# Edison_Mezzanine_ArduinoPro.net
KiCad netlist of a schematic drawn in EAGLE
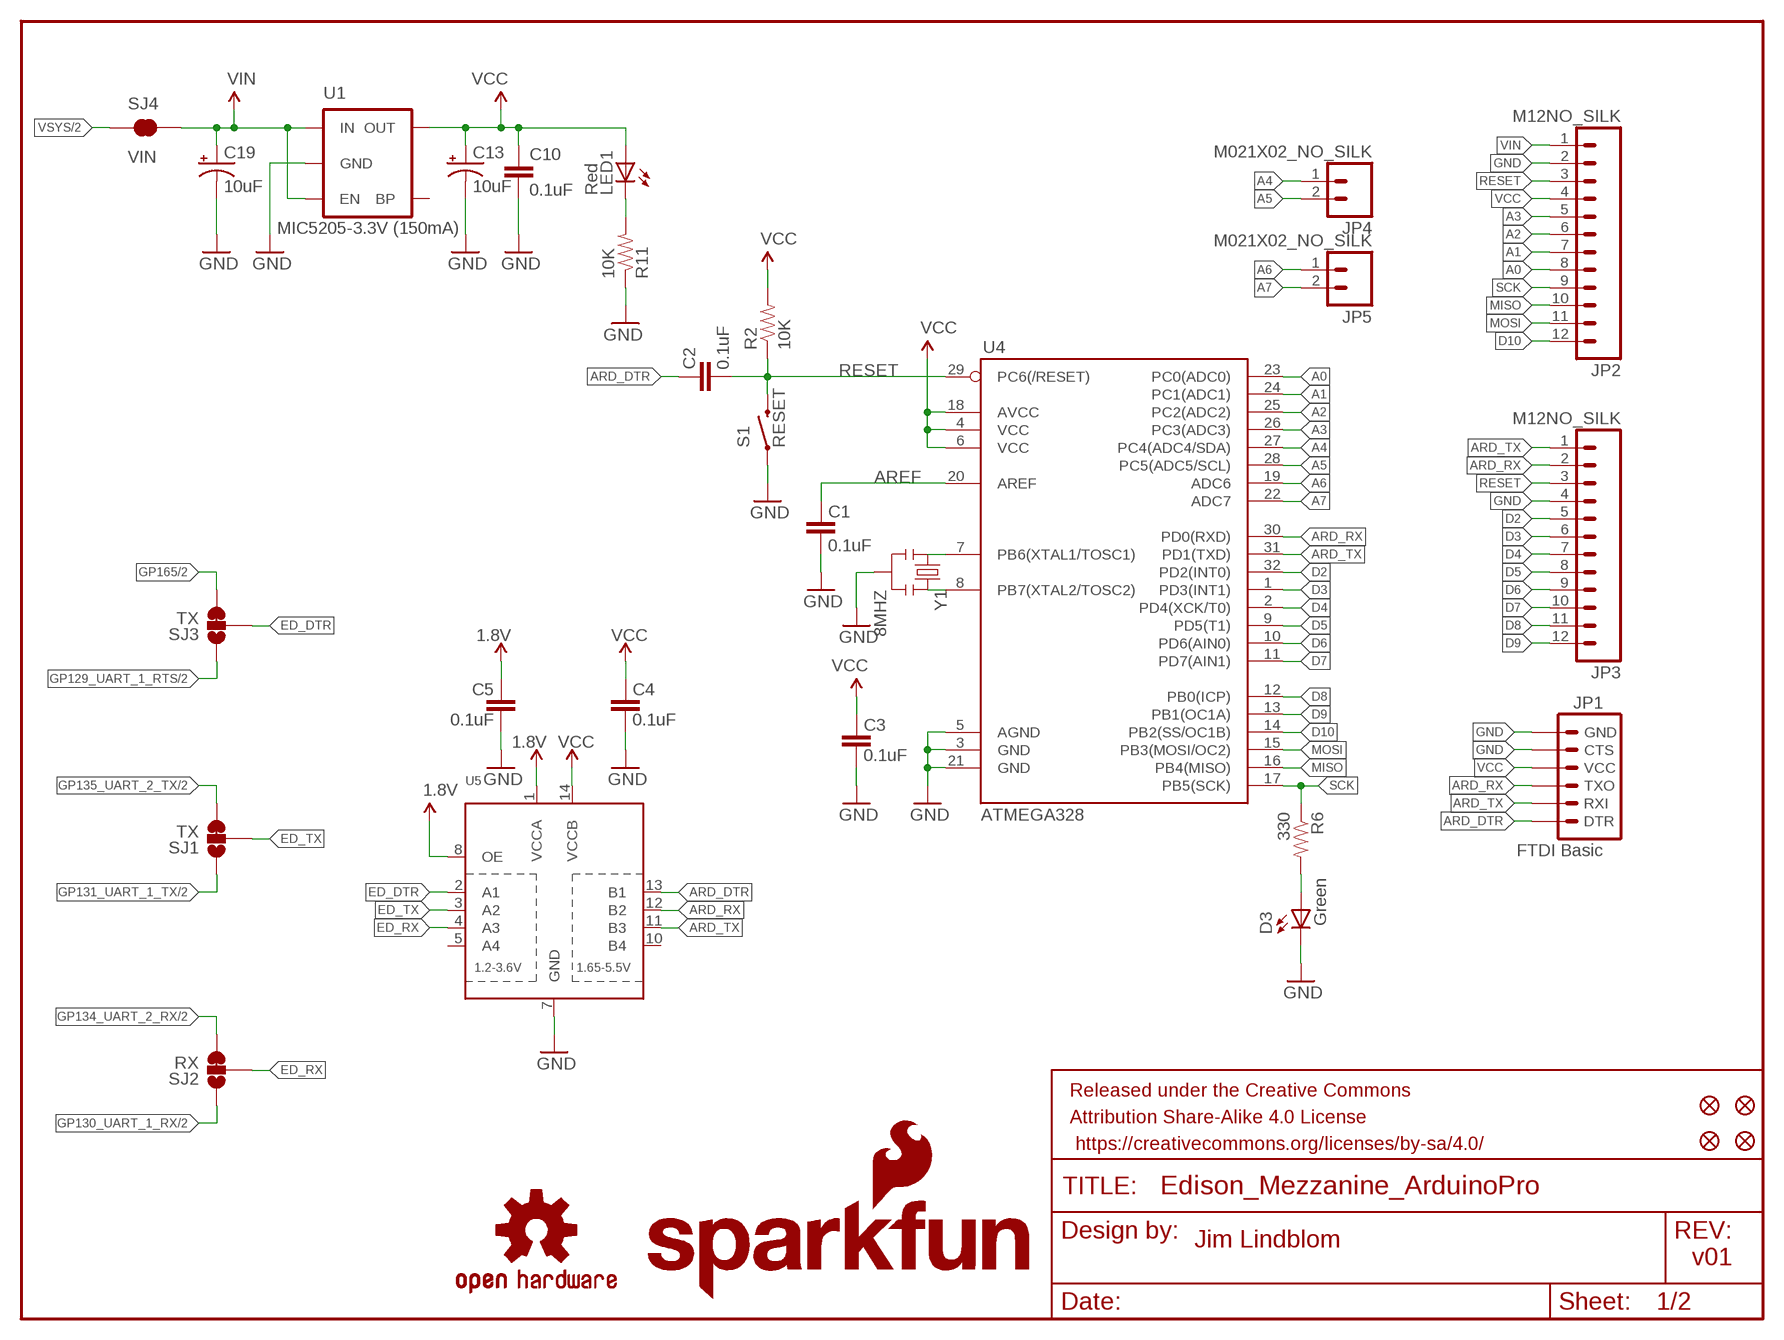
[diagram p0: schematic, sheet 1]
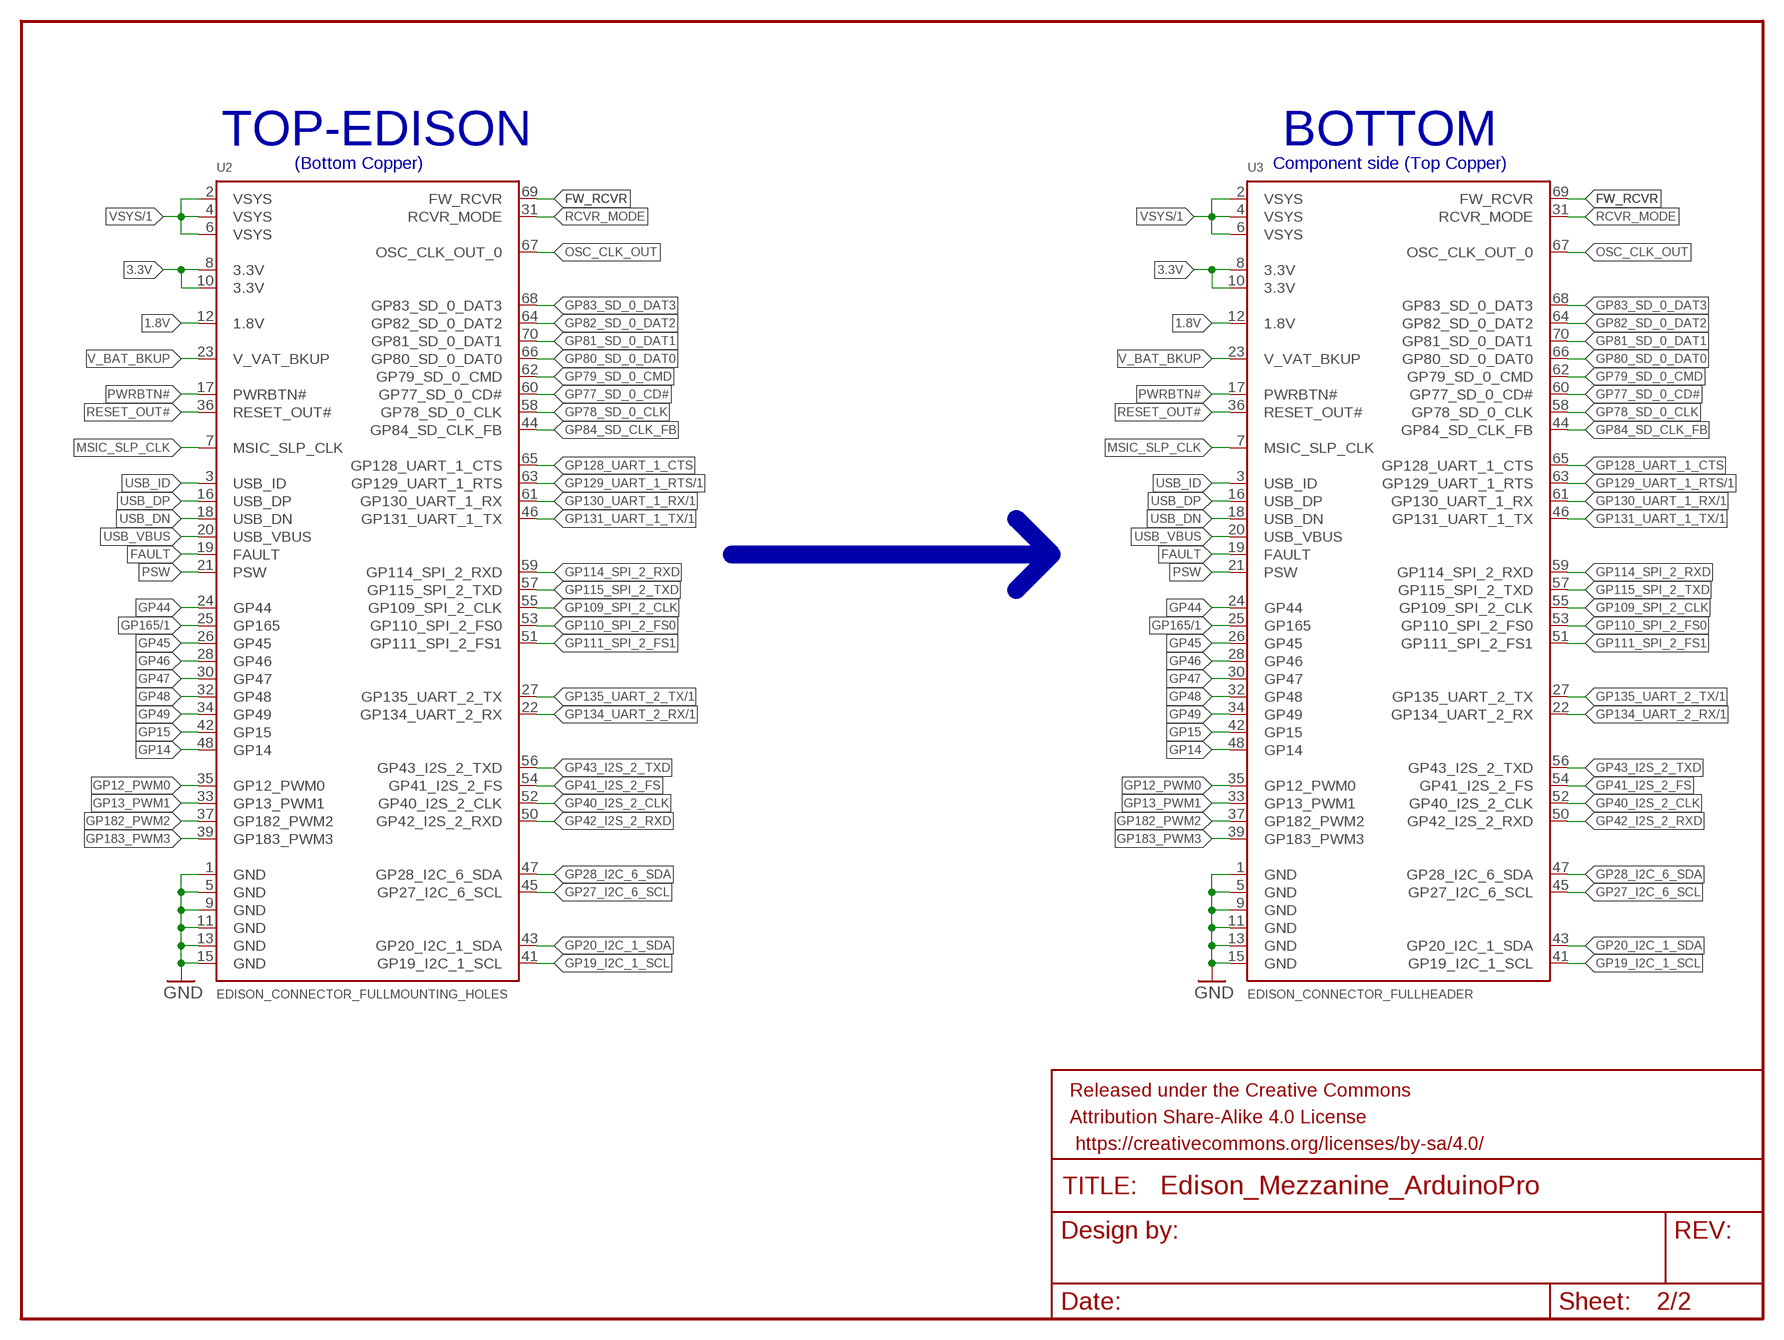
[diagram p1: schematic, sheet 2]

(export (version "E")
  (design (tool "Eeschema 10.0.6"))
  (components
    (comp (ref "C1")
      (value "0.1uF")
      (footprint "eagle-import:0603-CAP")
      (libsource (lib "eagle-import") (part "CAP0603-CAP"))
    )
    (comp (ref "C2")
      (value "0.1uF")
      (footprint "eagle-import:0603-CAP")
      (libsource (lib "eagle-import") (part "CAP0603-CAP"))
    )
    (comp (ref "C3")
      (value "0.1uF")
      (footprint "eagle-import:0603-CAP")
      (libsource (lib "eagle-import") (part "CAP0603-CAP"))
    )
    (comp (ref "C4")
      (value "0.1uF")
      (footprint "eagle-import:0603-CAP")
      (libsource (lib "eagle-import") (part "CAP0603-CAP"))
    )
    (comp (ref "C5")
      (value "0.1uF")
      (footprint "eagle-import:0603-CAP")
      (libsource (lib "eagle-import") (part "CAP0603-CAP"))
    )
    (comp (ref "C10")
      (value "0.1uF")
      (footprint "eagle-import:0603-CAP")
      (libsource (lib "eagle-import") (part "CAP0603-CAP"))
    )
    (comp (ref "C13")
      (value "10uF")
      (footprint "eagle-import:EIA3216")
      (libsource (lib "eagle-import") (part "CAP_POL1206"))
    )
    (comp (ref "C19")
      (value "10uF")
      (footprint "eagle-import:EIA3216")
      (libsource (lib "eagle-import") (part "CAP_POL1206"))
    )
    (comp (ref "D3")
      (value "Green")
      (footprint "eagle-import:0603-LED-ALT1")
      (libsource (lib "eagle-import") (part "LED"))
    )
    (comp (ref "FID1")
      (value "FIDUCIAL1X2")
      (footprint "eagle-import:FIDUCIAL-1X2")
      (libsource (lib "eagle-import") (part "FIDUCIAL1X2"))
    )
    (comp (ref "FID2")
      (value "FIDUCIAL1X2")
      (footprint "eagle-import:FIDUCIAL-1X2")
      (libsource (lib "eagle-import") (part "FIDUCIAL1X2"))
    )
    (comp (ref "FID3")
      (value "FIDUCIAL1X2")
      (footprint "eagle-import:FIDUCIAL-1X2")
      (libsource (lib "eagle-import") (part "FIDUCIAL1X2"))
    )
    (comp (ref "FID4")
      (value "FIDUCIAL1X2")
      (footprint "eagle-import:FIDUCIAL-1X2")
      (libsource (lib "eagle-import") (part "FIDUCIAL1X2"))
    )
    (comp (ref "FRAME1")
      (value "FRAME-LETTER")
      (footprint "eagle-import:CREATIVE_COMMONS")
      (libsource (lib "eagle-import") (part "FRAME-LETTER"))
    )
    (comp (ref "JP1")
      (value "FTDI Basic")
      (footprint "eagle-import:1X06")
      (libsource (lib "eagle-import") (part "ARDUINO_SERIAL_PROGRAMPTH"))
    )
    (comp (ref "JP2")
      (value "M12NO_SILK")
      (footprint "eagle-import:1X12_NO_SILK")
      (libsource (lib "eagle-import") (part "M12NO_SILK"))
    )
    (comp (ref "JP3")
      (value "M12NO_SILK")
      (footprint "eagle-import:1X12_NO_SILK")
      (libsource (lib "eagle-import") (part "M12NO_SILK"))
    )
    (comp (ref "JP4")
      (value "M021X02_NO_SILK")
      (footprint "eagle-import:1X02_NO_SILK")
      (libsource (lib "eagle-import") (part "M021X02_NO_SILK"))
    )
    (comp (ref "JP5")
      (value "M021X02_NO_SILK")
      (footprint "eagle-import:1X02_NO_SILK")
      (libsource (lib "eagle-import") (part "M021X02_NO_SILK"))
    )
    (comp (ref "LED1")
      (value "Red")
      (footprint "eagle-import:0603-LED-ALT1")
      (libsource (lib "eagle-import") (part "LED"))
    )
    (comp (ref "LOGO1")
      (value "OSHW-LOGOS")
      (footprint "eagle-import:OSHW-LOGO-S")
      (libsource (lib "eagle-import") (part "OSHW-LOGOS"))
    )
    (comp (ref "LOGO4")
      (value "SFE_LOGO_NAME_FLAME.1_INCH")
      (footprint "eagle-import:SFE_LOGO_NAME_FLAME_.1")
      (libsource (lib "eagle-import") (part "SFE_LOGO_NAME_FLAME.1_INCH"))
    )
    (comp (ref "R2")
      (value "10K")
      (footprint "eagle-import:0603-RES")
      (libsource (lib "eagle-import") (part "RESISTOR0603-RES"))
    )
    (comp (ref "R6")
      (value "330")
      (footprint "eagle-import:0603-RES")
      (libsource (lib "eagle-import") (part "RESISTOR0603-RES"))
    )
    (comp (ref "R11")
      (value "10K")
      (footprint "eagle-import:0603-RES")
      (libsource (lib "eagle-import") (part "RESISTOR0603-RES"))
    )
    (comp (ref "S1")
      (value "RESET")
      (footprint "eagle-import:TACTILE-SWITCH-1101NE")
      (libsource (lib "eagle-import") (part "SWITCH-MOMENTARY-2-SMD-1101NE"))
    )
    (comp (ref "SJ1")
      (value "TX")
      (footprint "eagle-import:PAD-JUMPER-3-2OF3_NC_BY_TRACE_YES_SILK_FULL_BOX")
      (libsource (lib "eagle-import") (part "JUMPER-PAD-3-2OF3_NC_BY_TRACE"))
    )
    (comp (ref "SJ2")
      (value "RX")
      (footprint "eagle-import:PAD-JUMPER-3-2OF3_NC_BY_TRACE_YES_SILK_FULL_BOX")
      (libsource (lib "eagle-import") (part "JUMPER-PAD-3-2OF3_NC_BY_TRACE"))
    )
    (comp (ref "SJ3")
      (value "TX")
      (footprint "eagle-import:PAD-JUMPER-3-2OF3_NC_BY_TRACE_YES_SILK_FULL_BOX")
      (libsource (lib "eagle-import") (part "JUMPER-PAD-3-2OF3_NC_BY_TRACE"))
    )
    (comp (ref "SJ4")
      (value "VIN")
      (footprint "eagle-import:PAD-JUMPER-2-NC_BY_TRACE_YES_SILK")
      (libsource (lib "eagle-import") (part "JUMPER-PAD-2-NC_BY_TRACE"))
    )
    (comp (ref "U1")
      (value "MIC5205-3.3V (150mA)")
      (footprint "eagle-import:SOT23-5")
      (libsource (lib "eagle-import") (part "V_REG_LDOSMD"))
    )
    (comp (ref "U4")
      (value "ATMEGA328")
      (footprint "eagle-import:TQFP32-08")
      (libsource (lib "eagle-import") (part "ATMEGA168"))
    )
    (comp (ref "U5")
      (value "TXB0104PWRSOIC14")
      (footprint "eagle-import:SO14")
      (libsource (lib "eagle-import") (part "TXB0104PWRSOIC14"))
    )
    (comp (ref "Y1")
      (value "8MHZ")
      (footprint "eagle-import:RESONATOR-SMD")
      (libsource (lib "eagle-import") (part "RESONATOR8MHZ"))
    )
    (comp (ref "FRAME2")
      (value "FRAME-LETTER")
      (footprint "eagle-import:CREATIVE_COMMONS")
      (libsource (lib "eagle-import") (part "FRAME-LETTER"))
    )
    (comp (ref "U2")
      (value "EDISON_CONNECTOR_FULLMOUNTING_HOLES")
      (footprint "eagle-import:EDISON_DAUGHTER")
      (libsource (lib "eagle-import") (part "EDISON_CONNECTOR_FULLMOUNTING_HOLES"))
    )
    (comp (ref "U3")
      (value "EDISON_CONNECTOR_FULLHEADER")
      (footprint "eagle-import:DF40C-70DP-0.4(51)")
      (libsource (lib "eagle-import") (part "EDISON_CONNECTOR_FULLHEADER"))
    )
  )
  (nets
    (net (code "1") (name "1.8V") (class "Default")
      (node (ref "C5") (pin "2") (pinfunction "2_2") (pintype "passive"))
      (node (ref "U2") (pin "12") (pinfunction "1.8V_12") (pintype "bidirectional"))
      (node (ref "U3") (pin "12") (pinfunction "1.8V_12") (pintype "bidirectional"))
      (node (ref "U5") (pin "1") (pinfunction "VCCA_1") (pintype "bidirectional"))
      (node (ref "U5") (pin "8") (pinfunction "OE_8") (pintype "bidirectional"))
    )
    (net (code "2") (name "3.3V") (class "Default")
      (node (ref "U2") (pin "10") (pinfunction "3.3V_10") (pintype "bidirectional"))
      (node (ref "U2") (pin "8") (pinfunction "3.3V_8") (pintype "bidirectional"))
      (node (ref "U3") (pin "10") (pinfunction "3.3V_10") (pintype "bidirectional"))
      (node (ref "U3") (pin "8") (pinfunction "3.3V_8") (pintype "bidirectional"))
    )
    (net (code "3") (name "A0") (class "Default")
      (node (ref "JP2") (pin "8") (pinfunction "8_8") (pintype "passive"))
      (node (ref "U4") (pin "23") (pinfunction "PC0(ADC0)_23") (pintype "bidirectional"))
    )
    (net (code "4") (name "A1") (class "Default")
      (node (ref "JP2") (pin "7") (pinfunction "7_7") (pintype "passive"))
      (node (ref "U4") (pin "24") (pinfunction "PC1(ADC1)_24") (pintype "bidirectional"))
    )
    (net (code "5") (name "A2") (class "Default")
      (node (ref "JP2") (pin "6") (pinfunction "6_6") (pintype "passive"))
      (node (ref "U4") (pin "25") (pinfunction "PC2(ADC2)_25") (pintype "bidirectional"))
    )
    (net (code "6") (name "A3") (class "Default")
      (node (ref "JP2") (pin "5") (pinfunction "5_5") (pintype "passive"))
      (node (ref "U4") (pin "26") (pinfunction "PC3(ADC3)_26") (pintype "bidirectional"))
    )
    (net (code "7") (name "A4") (class "Default")
      (node (ref "JP4") (pin "1") (pinfunction "1_1") (pintype "passive"))
      (node (ref "U4") (pin "27") (pinfunction "PC4(ADC4/SDA)_27") (pintype "bidirectional"))
    )
    (net (code "8") (name "A5") (class "Default")
      (node (ref "JP4") (pin "2") (pinfunction "2_2") (pintype "passive"))
      (node (ref "U4") (pin "28") (pinfunction "PC5(ADC5/SCL)_28") (pintype "bidirectional"))
    )
    (net (code "9") (name "A6") (class "Default")
      (node (ref "JP5") (pin "1") (pinfunction "1_1") (pintype "passive"))
      (node (ref "U4") (pin "19") (pinfunction "ADC6_19") (pintype "bidirectional"))
    )
    (net (code "10") (name "A7") (class "Default")
      (node (ref "JP5") (pin "2") (pinfunction "2_2") (pintype "passive"))
      (node (ref "U4") (pin "22") (pinfunction "ADC7_22") (pintype "bidirectional"))
    )
    (net (code "11") (name "ARD_DTR") (class "Default")
      (node (ref "C2") (pin "2") (pinfunction "2_2") (pintype "passive"))
      (node (ref "JP1") (pin "1") (pinfunction "DTR_1") (pintype "passive"))
      (node (ref "U5") (pin "13") (pinfunction "B1_13") (pintype "bidirectional"))
    )
    (net (code "12") (name "ARD_RX") (class "Default")
      (node (ref "JP1") (pin "3") (pinfunction "TXO_3") (pintype "passive"))
      (node (ref "JP3") (pin "2") (pinfunction "2_2") (pintype "passive"))
      (node (ref "U4") (pin "30") (pinfunction "PD0(RXD)_30") (pintype "bidirectional"))
      (node (ref "U5") (pin "12") (pinfunction "B2_12") (pintype "bidirectional"))
    )
    (net (code "13") (name "ARD_TX") (class "Default")
      (node (ref "JP1") (pin "2") (pinfunction "RXI_2") (pintype "passive"))
      (node (ref "JP3") (pin "1") (pinfunction "1_1") (pintype "passive"))
      (node (ref "U4") (pin "31") (pinfunction "PD1(TXD)_31") (pintype "bidirectional"))
      (node (ref "U5") (pin "11") (pinfunction "B3_11") (pintype "bidirectional"))
    )
    (net (code "14") (name "AREF") (class "Default")
      (node (ref "C1") (pin "2") (pinfunction "2_2") (pintype "passive"))
      (node (ref "U4") (pin "20") (pinfunction "AREF_20") (pintype "bidirectional"))
    )
    (net (code "15") (name "D2") (class "Default")
      (node (ref "JP3") (pin "5") (pinfunction "5_5") (pintype "passive"))
      (node (ref "U4") (pin "32") (pinfunction "PD2(INT0)_32") (pintype "bidirectional"))
    )
    (net (code "16") (name "D3") (class "Default")
      (node (ref "JP3") (pin "6") (pinfunction "6_6") (pintype "passive"))
      (node (ref "U4") (pin "1") (pinfunction "PD3(INT1)_1") (pintype "bidirectional"))
    )
    (net (code "17") (name "D4") (class "Default")
      (node (ref "JP3") (pin "7") (pinfunction "7_7") (pintype "passive"))
      (node (ref "U4") (pin "2") (pinfunction "PD4(XCK/T0)_2") (pintype "bidirectional"))
    )
    (net (code "18") (name "D5") (class "Default")
      (node (ref "JP3") (pin "8") (pinfunction "8_8") (pintype "passive"))
      (node (ref "U4") (pin "9") (pinfunction "PD5(T1)_9") (pintype "bidirectional"))
    )
    (net (code "19") (name "D6") (class "Default")
      (node (ref "JP3") (pin "9") (pinfunction "9_9") (pintype "passive"))
      (node (ref "U4") (pin "10") (pinfunction "PD6(AIN0)_10") (pintype "bidirectional"))
    )
    (net (code "20") (name "D7") (class "Default")
      (node (ref "JP3") (pin "10") (pinfunction "10_10") (pintype "passive"))
      (node (ref "U4") (pin "11") (pinfunction "PD7(AIN1)_11") (pintype "bidirectional"))
    )
    (net (code "21") (name "D8") (class "Default")
      (node (ref "JP3") (pin "11") (pinfunction "11_11") (pintype "passive"))
      (node (ref "U4") (pin "12") (pinfunction "PB0(ICP)_12") (pintype "bidirectional"))
    )
    (net (code "22") (name "D9") (class "Default")
      (node (ref "JP3") (pin "12") (pinfunction "12_12") (pintype "passive"))
      (node (ref "U4") (pin "13") (pinfunction "PB1(OC1A)_13") (pintype "bidirectional"))
    )
    (net (code "23") (name "D10") (class "Default")
      (node (ref "JP2") (pin "12") (pinfunction "12_12") (pintype "passive"))
      (node (ref "U4") (pin "14") (pinfunction "PB2(SS/OC1B)_14") (pintype "bidirectional"))
    )
    (net (code "24") (name "ED_DTR") (class "Default")
      (node (ref "SJ3") (pin "2") (pinfunction "2_2") (pintype "passive"))
      (node (ref "U5") (pin "2") (pinfunction "A1_2") (pintype "bidirectional"))
    )
    (net (code "25") (name "ED_RX") (class "Default")
      (node (ref "SJ2") (pin "2") (pinfunction "2_2") (pintype "passive"))
      (node (ref "U5") (pin "4") (pinfunction "A3_4") (pintype "bidirectional"))
    )
    (net (code "26") (name "ED_TX") (class "Default")
      (node (ref "SJ1") (pin "2") (pinfunction "2_2") (pintype "passive"))
      (node (ref "U5") (pin "3") (pinfunction "A2_3") (pintype "bidirectional"))
    )
    (net (code "27") (name "FAULT") (class "Default")
      (node (ref "U2") (pin "19") (pinfunction "FAULT_19") (pintype "bidirectional"))
      (node (ref "U3") (pin "19") (pinfunction "FAULT_19") (pintype "bidirectional"))
    )
    (net (code "28") (name "FW_RCVR") (class "Default")
      (node (ref "U2") (pin "69") (pinfunction "FW_RCVR_69") (pintype "bidirectional"))
      (node (ref "U3") (pin "69") (pinfunction "FW_RCVR_69") (pintype "bidirectional"))
    )
    (net (code "29") (name "GND") (class "Default")
      (node (ref "C1") (pin "1") (pinfunction "1_1") (pintype "passive"))
      (node (ref "C10") (pin "2") (pinfunction "2_2") (pintype "passive"))
      (node (ref "C13") (pin "C") (pinfunction "-_C") (pintype "passive"))
      (node (ref "C19") (pin "C") (pinfunction "-_C") (pintype "passive"))
      (node (ref "C3") (pin "1") (pinfunction "1_1") (pintype "passive"))
      (node (ref "C4") (pin "1") (pinfunction "1_1") (pintype "passive"))
      (node (ref "C5") (pin "1") (pinfunction "1_1") (pintype "passive"))
      (node (ref "D3") (pin "C") (pinfunction "C_C") (pintype "passive"))
      (node (ref "JP1") (pin "5") (pinfunction "CTS_5") (pintype "passive"))
      (node (ref "JP1") (pin "6") (pinfunction "GND_6") (pintype "passive"))
      (node (ref "JP2") (pin "2") (pinfunction "2_2") (pintype "passive"))
      (node (ref "JP3") (pin "4") (pinfunction "4_4") (pintype "passive"))
      (node (ref "R11") (pin "1") (pinfunction "1_1") (pintype "passive"))
      (node (ref "S1") (pin "P$1") (pinfunction "1_P$1") (pintype "passive"))
      (node (ref "U1") (pin "2") (pinfunction "GND_2") (pintype "input"))
      (node (ref "U2") (pin "1") (pinfunction "GND_1") (pintype "bidirectional"))
      (node (ref "U2") (pin "11") (pinfunction "GND_11") (pintype "bidirectional"))
      (node (ref "U2") (pin "13") (pinfunction "GND_13") (pintype "bidirectional"))
      (node (ref "U2") (pin "15") (pinfunction "GND_15") (pintype "bidirectional"))
      (node (ref "U2") (pin "5") (pinfunction "GND_5") (pintype "bidirectional"))
      (node (ref "U2") (pin "9") (pinfunction "GND_9") (pintype "bidirectional"))
      (node (ref "U3") (pin "1") (pinfunction "GND_1") (pintype "bidirectional"))
      (node (ref "U3") (pin "11") (pinfunction "GND_11") (pintype "bidirectional"))
      (node (ref "U3") (pin "13") (pinfunction "GND_13") (pintype "bidirectional"))
      (node (ref "U3") (pin "15") (pinfunction "GND_15") (pintype "bidirectional"))
      (node (ref "U3") (pin "5") (pinfunction "GND_5") (pintype "bidirectional"))
      (node (ref "U3") (pin "9") (pinfunction "GND_9") (pintype "bidirectional"))
      (node (ref "U4") (pin "21") (pinfunction "GND_21") (pintype "bidirectional"))
      (node (ref "U4") (pin "3") (pinfunction "GND_3") (pintype "bidirectional"))
      (node (ref "U4") (pin "5") (pinfunction "AGND_5") (pintype "bidirectional"))
      (node (ref "U5") (pin "7") (pinfunction "GND_7") (pintype "bidirectional"))
      (node (ref "Y1") (pin "2") (pinfunction "2_2") (pintype "passive"))
    )
    (net (code "30") (name "GP12_PWM0") (class "Default")
      (node (ref "U2") (pin "35") (pinfunction "GP12_PWM0_35") (pintype "bidirectional"))
      (node (ref "U3") (pin "35") (pinfunction "GP12_PWM0_35") (pintype "bidirectional"))
    )
    (net (code "31") (name "GP13_PWM1") (class "Default")
      (node (ref "U2") (pin "33") (pinfunction "GP13_PWM1_33") (pintype "bidirectional"))
      (node (ref "U3") (pin "33") (pinfunction "GP13_PWM1_33") (pintype "bidirectional"))
    )
    (net (code "32") (name "GP14") (class "Default")
      (node (ref "U2") (pin "48") (pinfunction "GP14_48") (pintype "bidirectional"))
      (node (ref "U3") (pin "48") (pinfunction "GP14_48") (pintype "bidirectional"))
    )
    (net (code "33") (name "GP15") (class "Default")
      (node (ref "U2") (pin "42") (pinfunction "GP15_42") (pintype "bidirectional"))
      (node (ref "U3") (pin "42") (pinfunction "GP15_42") (pintype "bidirectional"))
    )
    (net (code "34") (name "GP19_I2C_1_SCL") (class "Default")
      (node (ref "U2") (pin "41") (pinfunction "GP19_I2C_1_SCL_41") (pintype "bidirectional"))
      (node (ref "U3") (pin "41") (pinfunction "GP19_I2C_1_SCL_41") (pintype "bidirectional"))
    )
    (net (code "35") (name "GP20_I2C_1_SDA") (class "Default")
      (node (ref "U2") (pin "43") (pinfunction "GP20_I2C_1_SDA_43") (pintype "bidirectional"))
      (node (ref "U3") (pin "43") (pinfunction "GP20_I2C_1_SDA_43") (pintype "bidirectional"))
    )
    (net (code "36") (name "GP27_I2C_6_SCL") (class "Default")
      (node (ref "U2") (pin "45") (pinfunction "GP27_I2C_6_SCL_45") (pintype "bidirectional"))
      (node (ref "U3") (pin "45") (pinfunction "GP27_I2C_6_SCL_45") (pintype "bidirectional"))
    )
    (net (code "37") (name "GP28_I2C_6_SDA") (class "Default")
      (node (ref "U2") (pin "47") (pinfunction "GP28_I2C_6_SDA_47") (pintype "bidirectional"))
      (node (ref "U3") (pin "47") (pinfunction "GP28_I2C_6_SDA_47") (pintype "bidirectional"))
    )
    (net (code "38") (name "GP40_I2S_2_CLK") (class "Default")
      (node (ref "U2") (pin "52") (pinfunction "GP40_I2S_2_CLK_52") (pintype "bidirectional"))
      (node (ref "U3") (pin "52") (pinfunction "GP40_I2S_2_CLK_52") (pintype "bidirectional"))
    )
    (net (code "39") (name "GP41_I2S_2_FS") (class "Default")
      (node (ref "U2") (pin "54") (pinfunction "GP41_I2S_2_FS_54") (pintype "bidirectional"))
      (node (ref "U3") (pin "54") (pinfunction "GP41_I2S_2_FS_54") (pintype "bidirectional"))
    )
    (net (code "40") (name "GP42_I2S_2_RXD") (class "Default")
      (node (ref "U2") (pin "50") (pinfunction "GP42_I2S_2_RXD_50") (pintype "bidirectional"))
      (node (ref "U3") (pin "50") (pinfunction "GP42_I2S_2_RXD_50") (pintype "bidirectional"))
    )
    (net (code "41") (name "GP43_I2S_2_TXD") (class "Default")
      (node (ref "U2") (pin "56") (pinfunction "GP43_I2S_2_TXD_56") (pintype "bidirectional"))
      (node (ref "U3") (pin "56") (pinfunction "GP43_I2S_2_TXD_56") (pintype "bidirectional"))
    )
    (net (code "42") (name "GP44") (class "Default")
      (node (ref "U2") (pin "24") (pinfunction "GP44_24") (pintype "bidirectional"))
      (node (ref "U3") (pin "24") (pinfunction "GP44_24") (pintype "bidirectional"))
    )
    (net (code "43") (name "GP45") (class "Default")
      (node (ref "U2") (pin "26") (pinfunction "GP45_26") (pintype "bidirectional"))
      (node (ref "U3") (pin "26") (pinfunction "GP45_26") (pintype "bidirectional"))
    )
    (net (code "44") (name "GP46") (class "Default")
      (node (ref "U2") (pin "28") (pinfunction "GP46_28") (pintype "bidirectional"))
      (node (ref "U3") (pin "28") (pinfunction "GP46_28") (pintype "bidirectional"))
    )
    (net (code "45") (name "GP47") (class "Default")
      (node (ref "U2") (pin "30") (pinfunction "GP47_30") (pintype "bidirectional"))
      (node (ref "U3") (pin "30") (pinfunction "GP47_30") (pintype "bidirectional"))
    )
    (net (code "46") (name "GP48") (class "Default")
      (node (ref "U2") (pin "32") (pinfunction "GP48_32") (pintype "bidirectional"))
      (node (ref "U3") (pin "32") (pinfunction "GP48_32") (pintype "bidirectional"))
    )
    (net (code "47") (name "GP49") (class "Default")
      (node (ref "U2") (pin "34") (pinfunction "GP49_34") (pintype "bidirectional"))
      (node (ref "U3") (pin "34") (pinfunction "GP49_34") (pintype "bidirectional"))
    )
    (net (code "48") (name "GP77_SD_0_CD#") (class "Default")
      (node (ref "U2") (pin "60") (pinfunction "GP77_SD_0_CD#_60") (pintype "bidirectional"))
      (node (ref "U3") (pin "60") (pinfunction "GP77_SD_0_CD#_60") (pintype "bidirectional"))
    )
    (net (code "49") (name "GP78_SD_0_CLK") (class "Default")
      (node (ref "U2") (pin "58") (pinfunction "GP78_SD_0_CLK_58") (pintype "bidirectional"))
      (node (ref "U3") (pin "58") (pinfunction "GP78_SD_0_CLK_58") (pintype "bidirectional"))
    )
    (net (code "50") (name "GP79_SD_0_CMD") (class "Default")
      (node (ref "U2") (pin "62") (pinfunction "GP79_SD_0_CMD_62") (pintype "bidirectional"))
      (node (ref "U3") (pin "62") (pinfunction "GP79_SD_0_CMD_62") (pintype "bidirectional"))
    )
    (net (code "51") (name "GP80_SD_0_DAT0") (class "Default")
      (node (ref "U2") (pin "66") (pinfunction "GP80_SD_0_DAT0_66") (pintype "bidirectional"))
      (node (ref "U3") (pin "66") (pinfunction "GP80_SD_0_DAT0_66") (pintype "bidirectional"))
    )
    (net (code "52") (name "GP81_SD_0_DAT1") (class "Default")
      (node (ref "U2") (pin "70") (pinfunction "GP81_SD_0_DAT1_70") (pintype "bidirectional"))
      (node (ref "U3") (pin "70") (pinfunction "GP81_SD_0_DAT1_70") (pintype "bidirectional"))
    )
    (net (code "53") (name "GP82_SD_0_DAT2") (class "Default")
      (node (ref "U2") (pin "64") (pinfunction "GP82_SD_0_DAT2_64") (pintype "bidirectional"))
      (node (ref "U3") (pin "64") (pinfunction "GP82_SD_0_DAT2_64") (pintype "bidirectional"))
    )
    (net (code "54") (name "GP83_SD_0_DAT3") (class "Default")
      (node (ref "U2") (pin "68") (pinfunction "GP83_SD_0_DAT3_68") (pintype "bidirectional"))
      (node (ref "U3") (pin "68") (pinfunction "GP83_SD_0_DAT3_68") (pintype "bidirectional"))
    )
    (net (code "55") (name "GP84_SD_CLK_FB") (class "Default")
      (node (ref "U2") (pin "44") (pinfunction "GP84_SD_CLK_FB_44") (pintype "bidirectional"))
      (node (ref "U3") (pin "44") (pinfunction "GP84_SD_CLK_FB_44") (pintype "bidirectional"))
    )
    (net (code "56") (name "GP109_SPI_2_CLK") (class "Default")
      (node (ref "U2") (pin "55") (pinfunction "GP109_SPI_2_CLK_55") (pintype "bidirectional"))
      (node (ref "U3") (pin "55") (pinfunction "GP109_SPI_2_CLK_55") (pintype "bidirectional"))
    )
    (net (code "57") (name "GP110_SPI_2_FS0") (class "Default")
      (node (ref "U2") (pin "53") (pinfunction "GP110_SPI_2_FS0_53") (pintype "bidirectional"))
      (node (ref "U3") (pin "53") (pinfunction "GP110_SPI_2_FS0_53") (pintype "bidirectional"))
    )
    (net (code "58") (name "GP111_SPI_2_FS1") (class "Default")
      (node (ref "U2") (pin "51") (pinfunction "GP111_SPI_2_FS1_51") (pintype "bidirectional"))
      (node (ref "U3") (pin "51") (pinfunction "GP111_SPI_2_FS1_51") (pintype "bidirectional"))
    )
    (net (code "59") (name "GP114_SPI_2_RXD") (class "Default")
      (node (ref "U2") (pin "59") (pinfunction "GP114_SPI_2_RXD_59") (pintype "bidirectional"))
      (node (ref "U3") (pin "59") (pinfunction "GP114_SPI_2_RXD_59") (pintype "bidirectional"))
    )
    (net (code "60") (name "GP115_SPI_2_TXD") (class "Default")
      (node (ref "U2") (pin "57") (pinfunction "GP115_SPI_2_TXD_57") (pintype "bidirectional"))
      (node (ref "U3") (pin "57") (pinfunction "GP115_SPI_2_TXD_57") (pintype "bidirectional"))
    )
    (net (code "61") (name "GP128_UART_1_CTS") (class "Default")
      (node (ref "U2") (pin "65") (pinfunction "GP128_UART_1_CTS_65") (pintype "bidirectional"))
      (node (ref "U3") (pin "65") (pinfunction "GP128_UART_1_CTS_65") (pintype "bidirectional"))
    )
    (net (code "62") (name "GP129_UART_1_RTS") (class "Default")
      (node (ref "SJ3") (pin "1") (pinfunction "1_1") (pintype "passive"))
      (node (ref "U2") (pin "63") (pinfunction "GP129_UART_1_RTS_63") (pintype "bidirectional"))
      (node (ref "U3") (pin "63") (pinfunction "GP129_UART_1_RTS_63") (pintype "bidirectional"))
    )
    (net (code "63") (name "GP130_UART_1_RX") (class "Default")
      (node (ref "SJ2") (pin "1") (pinfunction "1_1") (pintype "passive"))
      (node (ref "U2") (pin "61") (pinfunction "GP130_UART_1_RX_61") (pintype "bidirectional"))
      (node (ref "U3") (pin "61") (pinfunction "GP130_UART_1_RX_61") (pintype "bidirectional"))
    )
    (net (code "64") (name "GP131_UART_1_TX") (class "Default")
      (node (ref "SJ1") (pin "1") (pinfunction "1_1") (pintype "passive"))
      (node (ref "U2") (pin "46") (pinfunction "GP131_UART_1_TX_46") (pintype "bidirectional"))
      (node (ref "U3") (pin "46") (pinfunction "GP131_UART_1_TX_46") (pintype "bidirectional"))
    )
    (net (code "65") (name "GP134_UART_2_RX") (class "Default")
      (node (ref "SJ2") (pin "3") (pinfunction "3_3") (pintype "passive"))
      (node (ref "U2") (pin "22") (pinfunction "GP134_UART_2_RX_22") (pintype "bidirectional"))
      (node (ref "U3") (pin "22") (pinfunction "GP134_UART_2_RX_22") (pintype "bidirectional"))
    )
    (net (code "66") (name "GP135_UART_2_TX") (class "Default")
      (node (ref "SJ1") (pin "3") (pinfunction "3_3") (pintype "passive"))
      (node (ref "U2") (pin "27") (pinfunction "GP135_UART_2_TX_27") (pintype "bidirectional"))
      (node (ref "U3") (pin "27") (pinfunction "GP135_UART_2_TX_27") (pintype "bidirectional"))
    )
    (net (code "67") (name "GP165") (class "Default")
      (node (ref "SJ3") (pin "3") (pinfunction "3_3") (pintype "passive"))
      (node (ref "U2") (pin "25") (pinfunction "GP165_25") (pintype "bidirectional"))
      (node (ref "U3") (pin "25") (pinfunction "GP165_25") (pintype "bidirectional"))
    )
    (net (code "68") (name "GP182_PWM2") (class "Default")
      (node (ref "U2") (pin "37") (pinfunction "GP182_PWM2_37") (pintype "bidirectional"))
      (node (ref "U3") (pin "37") (pinfunction "GP182_PWM2_37") (pintype "bidirectional"))
    )
    (net (code "69") (name "GP183_PWM3") (class "Default")
      (node (ref "U2") (pin "39") (pinfunction "GP183_PWM3_39") (pintype "bidirectional"))
      (node (ref "U3") (pin "39") (pinfunction "GP183_PWM3_39") (pintype "bidirectional"))
    )
    (net (code "70") (name "MISO") (class "Default")
      (node (ref "JP2") (pin "10") (pinfunction "10_10") (pintype "passive"))
      (node (ref "U4") (pin "16") (pinfunction "PB4(MISO)_16") (pintype "bidirectional"))
    )
    (net (code "71") (name "MOSI") (class "Default")
      (node (ref "JP2") (pin "11") (pinfunction "11_11") (pintype "passive"))
      (node (ref "U4") (pin "15") (pinfunction "PB3(MOSI/OC2)_15") (pintype "bidirectional"))
    )
    (net (code "72") (name "MSIC_SLP_CLK") (class "Default")
      (node (ref "U2") (pin "7") (pinfunction "MSIC_SLP_CLK_7") (pintype "bidirectional"))
      (node (ref "U3") (pin "7") (pinfunction "MSIC_SLP_CLK_7") (pintype "bidirectional"))
    )
    (net (code "73") (name "Net-(D3-PadA)") (class "Default")
      (node (ref "D3") (pin "A") (pinfunction "A_A") (pintype "passive"))
      (node (ref "R6") (pin "2") (pinfunction "2_2") (pintype "passive"))
    )
    (net (code "74") (name "Net-(LED1-PadC)") (class "Default")
      (node (ref "LED1") (pin "C") (pinfunction "C_C") (pintype "passive"))
      (node (ref "R11") (pin "2") (pinfunction "2_2") (pintype "passive"))
    )
    (net (code "75") (name "Net-(U4-PB6(XTAL1{slash}TOSC1))") (class "Default")
      (node (ref "U4") (pin "7") (pinfunction "PB6(XTAL1/TOSC1)_7") (pintype "bidirectional"))
      (node (ref "Y1") (pin "1") (pinfunction "1_1") (pintype "passive"))
    )
    (net (code "76") (name "Net-(U4-PB7(XTAL2{slash}TOSC2))") (class "Default")
      (node (ref "U4") (pin "8") (pinfunction "PB7(XTAL2/TOSC2)_8") (pintype "bidirectional"))
      (node (ref "Y1") (pin "3") (pinfunction "3_3") (pintype "passive"))
    )
    (net (code "77") (name "OSC_CLK_OUT") (class "Default")
      (node (ref "U2") (pin "67") (pinfunction "OSC_CLK_OUT_0_67") (pintype "bidirectional"))
      (node (ref "U3") (pin "67") (pinfunction "OSC_CLK_OUT_0_67") (pintype "bidirectional"))
    )
    (net (code "78") (name "PSW") (class "Default")
      (node (ref "U2") (pin "21") (pinfunction "PSW_21") (pintype "bidirectional"))
      (node (ref "U3") (pin "21") (pinfunction "PSW_21") (pintype "bidirectional"))
    )
    (net (code "79") (name "PWRBTN#") (class "Default")
      (node (ref "U2") (pin "17") (pinfunction "PWRBTN#_17") (pintype "bidirectional"))
      (node (ref "U3") (pin "17") (pinfunction "PWRBTN#_17") (pintype "bidirectional"))
    )
    (net (code "80") (name "RCVR_MODE") (class "Default")
      (node (ref "U2") (pin "31") (pinfunction "RCVR_MODE_31") (pintype "bidirectional"))
      (node (ref "U3") (pin "31") (pinfunction "RCVR_MODE_31") (pintype "bidirectional"))
    )
    (net (code "81") (name "RESET") (class "Default")
      (node (ref "C2") (pin "1") (pinfunction "1_1") (pintype "passive"))
      (node (ref "JP2") (pin "3") (pinfunction "3_3") (pintype "passive"))
      (node (ref "JP3") (pin "3") (pinfunction "3_3") (pintype "passive"))
      (node (ref "R2") (pin "1") (pinfunction "1_1") (pintype "passive"))
      (node (ref "S1") (pin "P$2") (pinfunction "2_P$2") (pintype "passive"))
      (node (ref "U4") (pin "29") (pinfunction "PC6(/RESET)_29") (pintype "bidirectional"))
    )
    (net (code "82") (name "RESET_OUT#") (class "Default")
      (node (ref "U2") (pin "36") (pinfunction "RESET_OUT#_36") (pintype "bidirectional"))
      (node (ref "U3") (pin "36") (pinfunction "RESET_OUT#_36") (pintype "bidirectional"))
    )
    (net (code "83") (name "SCK") (class "Default")
      (node (ref "JP2") (pin "9") (pinfunction "9_9") (pintype "passive"))
      (node (ref "R6") (pin "1") (pinfunction "1_1") (pintype "passive"))
      (node (ref "U4") (pin "17") (pinfunction "PB5(SCK)_17") (pintype "bidirectional"))
    )
    (net (code "84") (name "USB_DN") (class "Default")
      (node (ref "U2") (pin "18") (pinfunction "USB_DN_18") (pintype "bidirectional"))
      (node (ref "U3") (pin "18") (pinfunction "USB_DN_18") (pintype "bidirectional"))
    )
    (net (code "85") (name "USB_DP") (class "Default")
      (node (ref "U2") (pin "16") (pinfunction "USB_DP_16") (pintype "bidirectional"))
      (node (ref "U3") (pin "16") (pinfunction "USB_DP_16") (pintype "bidirectional"))
    )
    (net (code "86") (name "USB_ID") (class "Default")
      (node (ref "U2") (pin "3") (pinfunction "USB_ID_3") (pintype "bidirectional"))
      (node (ref "U3") (pin "3") (pinfunction "USB_ID_3") (pintype "bidirectional"))
    )
    (net (code "87") (name "USB_VBUS") (class "Default")
      (node (ref "U2") (pin "20") (pinfunction "USB_VBUS_20") (pintype "bidirectional"))
      (node (ref "U3") (pin "20") (pinfunction "USB_VBUS_20") (pintype "bidirectional"))
    )
    (net (code "88") (name "VCC") (class "Default")
      (node (ref "C10") (pin "1") (pinfunction "1_1") (pintype "passive"))
      (node (ref "C13") (pin "A") (pinfunction "+_A") (pintype "passive"))
      (node (ref "C3") (pin "2") (pinfunction "2_2") (pintype "passive"))
      (node (ref "C4") (pin "2") (pinfunction "2_2") (pintype "passive"))
      (node (ref "JP1") (pin "4") (pinfunction "VCC_4") (pintype "passive"))
      (node (ref "JP2") (pin "4") (pinfunction "4_4") (pintype "passive"))
      (node (ref "LED1") (pin "A") (pinfunction "A_A") (pintype "passive"))
      (node (ref "R2") (pin "2") (pinfunction "2_2") (pintype "passive"))
      (node (ref "U1") (pin "5") (pinfunction "OUT_5") (pintype "passive"))
      (node (ref "U4") (pin "18") (pinfunction "AVCC_18") (pintype "bidirectional"))
      (node (ref "U4") (pin "4") (pinfunction "VCC_4") (pintype "bidirectional"))
      (node (ref "U4") (pin "6") (pinfunction "VCC_6") (pintype "bidirectional"))
      (node (ref "U5") (pin "14") (pinfunction "VCCB_14") (pintype "bidirectional"))
    )
    (net (code "89") (name "VIN") (class "Default")
      (node (ref "C19") (pin "A") (pinfunction "+_A") (pintype "passive"))
      (node (ref "JP2") (pin "1") (pinfunction "1_1") (pintype "passive"))
      (node (ref "SJ4") (pin "2") (pinfunction "2_2") (pintype "passive"))
      (node (ref "U1") (pin "1") (pinfunction "IN_1") (pintype "input"))
      (node (ref "U1") (pin "3") (pinfunction "EN_3") (pintype "input"))
    )
    (net (code "90") (name "VSYS") (class "Default")
      (node (ref "SJ4") (pin "1") (pinfunction "1_1") (pintype "passive"))
      (node (ref "U2") (pin "2") (pinfunction "VSYS_2") (pintype "bidirectional"))
      (node (ref "U2") (pin "4") (pinfunction "VSYS_4") (pintype "bidirectional"))
      (node (ref "U2") (pin "6") (pinfunction "VSYS_6") (pintype "bidirectional"))
      (node (ref "U3") (pin "2") (pinfunction "VSYS_2") (pintype "bidirectional"))
      (node (ref "U3") (pin "4") (pinfunction "VSYS_4") (pintype "bidirectional"))
      (node (ref "U3") (pin "6") (pinfunction "VSYS_6") (pintype "bidirectional"))
    )
    (net (code "91") (name "V_BAT_BKUP") (class "Default")
      (node (ref "U2") (pin "23") (pinfunction "V_VAT_BKUP_23") (pintype "bidirectional"))
      (node (ref "U3") (pin "23") (pinfunction "V_VAT_BKUP_23") (pintype "bidirectional"))
    )
    (net (code "92") (name "unconnected-(U1-BP-Pad4)") (class "Default")
      (node (ref "U1") (pin "4") (pinfunction "BP_4") (pintype "input"))
    )
    (net (code "93") (name "unconnected-(U5-A4-Pad5)") (class "Default")
      (node (ref "U5") (pin "5") (pinfunction "A4_5") (pintype "bidirectional"))
    )
    (net (code "94") (name "unconnected-(U5-B4-Pad10)") (class "Default")
      (node (ref "U5") (pin "10") (pinfunction "B4_10") (pintype "bidirectional"))
    )
  )
)
